# tweeq-Downloader_Basicv4.net
KiCad netlist of a schematic drawn in EAGLE
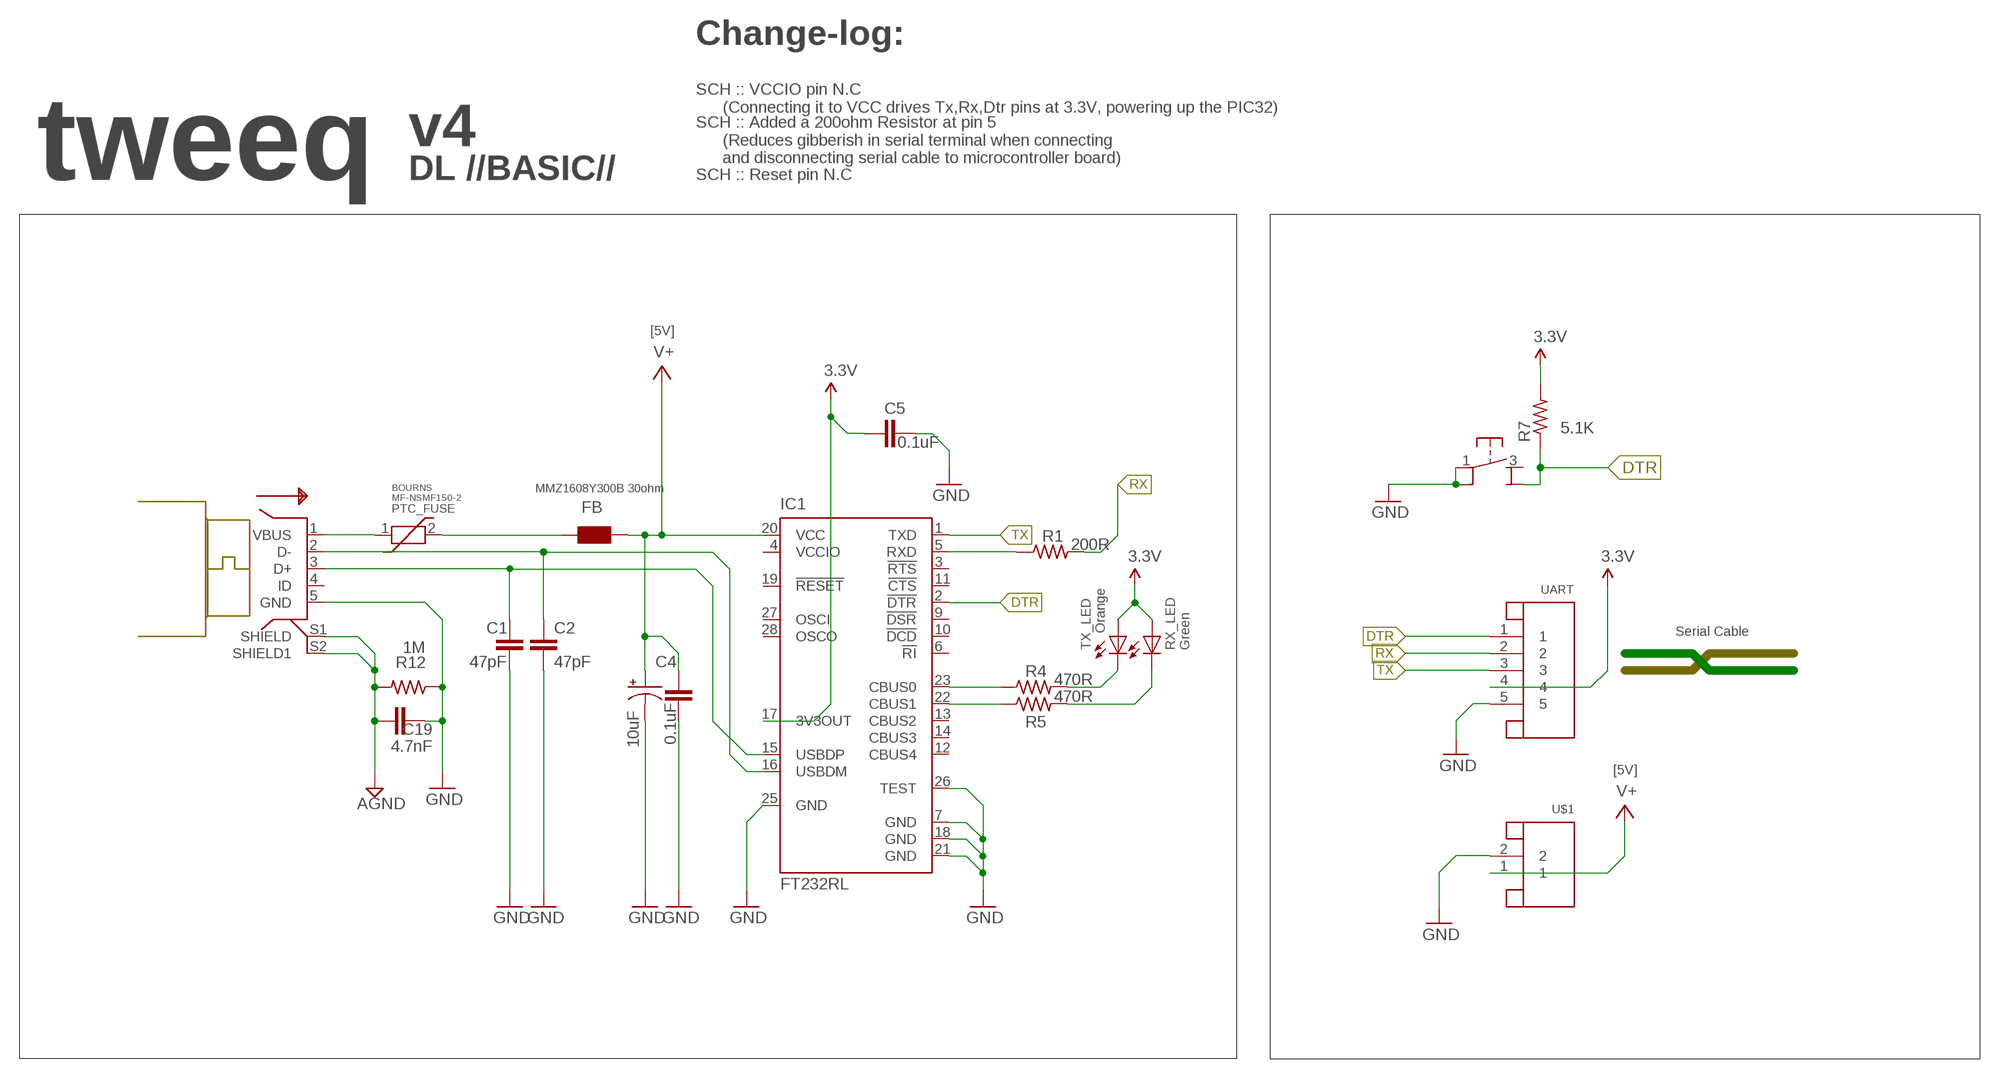
[diagram p0: schematic, sheet 1]

(export (version "E")
  (design (tool "Eeschema 10.0.6"))
  (components
    (comp (ref "C1")
      (value "47pF")
      (footprint "eagle-import:C0603K")
      (libsource (lib "eagle-import") (part "C-EUC0603K"))
    )
    (comp (ref "C2")
      (value "47pF")
      (footprint "eagle-import:C0603K")
      (libsource (lib "eagle-import") (part "C-EUC0603K"))
    )
    (comp (ref "C3")
      (value "10uF")
      (footprint "eagle-import:SMC_A")
      (libsource (lib "eagle-import") (part "CPOL-USSMCA"))
    )
    (comp (ref "C4")
      (value "0.1uF")
      (footprint "eagle-import:C0603K")
      (libsource (lib "eagle-import") (part "C-EUC0603K"))
    )
    (comp (ref "C5")
      (value "0.1uF")
      (footprint "eagle-import:C0603K")
      (libsource (lib "eagle-import") (part "C-EUC0603K"))
    )
    (comp (ref "C19")
      (value "4.7nF")
      (footprint "eagle-import:C0603K")
      (libsource (lib "eagle-import") (part "rcl_C-EUC0603K"))
    )
    (comp (ref "FB")
      (value "MMZ1608Y300B 30ohm")
      (footprint "eagle-import:0603")
      (libsource (lib "eagle-import") (part "WE-CBF_0603"))
    )
    (comp (ref "IC1")
      (value "FT232RL")
      (footprint "eagle-import:SSOP28")
      (libsource (lib "eagle-import") (part "FT232RL"))
    )
    (comp (ref "PTC_FUSE")
      (value "PTC_FUSE/MF-NSMF150-2")
      (footprint "eagle-import:1206F")
      (libsource (lib "eagle-import") (part "PTC_FUSE/MF-NSMF150-2"))
    )
    (comp (ref "R1")
      (value "200R")
      (footprint "eagle-import:R0603")
      (libsource (lib "eagle-import") (part "R-US_R0603"))
    )
    (comp (ref "R4")
      (value "470R")
      (footprint "eagle-import:R0603")
      (libsource (lib "eagle-import") (part "R-US_R0603"))
    )
    (comp (ref "R5")
      (value "470R")
      (footprint "eagle-import:R0603")
      (libsource (lib "eagle-import") (part "R-US_R0603"))
    )
    (comp (ref "R7")
      (value "5.1K")
      (footprint "eagle-import:R0603")
      (libsource (lib "eagle-import") (part "R-US_R0603"))
    )
    (comp (ref "R12")
      (value "1M")
      (footprint "eagle-import:R0603")
      (libsource (lib "eagle-import") (part "R-US_R0603"))
    )
    (comp (ref "RX_LED")
      (value "Green")
      (footprint "eagle-import:CHIP-LED0805")
      (libsource (lib "eagle-import") (part "LEDCHIP-LED0805"))
    )
    (comp (ref "TX_LED")
      (value "Orange")
      (footprint "eagle-import:CHIP-LED0805")
      (libsource (lib "eagle-import") (part "LEDCHIP-LED0805"))
    )
    (comp (ref "U$1")
      (value "JST-2PINSH")
      (footprint "eagle-import:SH1.0-2PIN")
      (libsource (lib "eagle-import") (part "JST-2PINSH"))
    )
    (comp (ref "U$2")
      (value "USB/MICRO-5PF-B")
      (footprint "eagle-import:MICRO_USB_5PF_B")
      (libsource (lib "eagle-import") (part "USB/MICRO-5PF-B"))
    )
    (comp (ref "U$4")
      (value "PB_MICRO_SMT")
      (footprint "eagle-import:PB_SMT_3.5X3X2")
      (libsource (lib "eagle-import") (part "PB_MICRO_SMT"))
    )
    (comp (ref "UART")
      (value "JST-5PINSH")
      (footprint "eagle-import:SH1.0-5PIN")
      (libsource (lib "eagle-import") (part "JST-5PINSH"))
    )
  )
  (nets
    (net (code "1") (name "/VCCIO") (class "Default")
      (node (ref "IC1") (pin "4") (pinfunction "VCCIO_4") (pintype "power_in"))
    )
    (net (code "2") (name "3.3V") (class "Default")
      (node (ref "C5") (pin "1") (pinfunction "1_1") (pintype "passive"))
      (node (ref "IC1") (pin "17") (pinfunction "3V3OUT_17") (pintype "output"))
      (node (ref "R7") (pin "2") (pinfunction "2_2") (pintype "passive"))
      (node (ref "RX_LED") (pin "A") (pinfunction "A_A") (pintype "passive"))
      (node (ref "TX_LED") (pin "A") (pinfunction "A_A") (pintype "passive"))
      (node (ref "UART") (pin "4") (pinfunction "4_4") (pintype "bidirectional"))
    )
    (net (code "3") (name "AGND") (class "Default")
      (node (ref "C19") (pin "2") (pinfunction "2_2") (pintype "passive"))
      (node (ref "R12") (pin "2") (pinfunction "2_2") (pintype "passive"))
      (node (ref "U$2") (pin "S1") (pinfunction "SHIELD_S1") (pintype "bidirectional"))
      (node (ref "U$2") (pin "S2") (pinfunction "SHIELD1_S2") (pintype "bidirectional"))
    )
    (net (code "4") (name "DTR") (class "Default")
      (node (ref "IC1") (pin "2") (pinfunction "~{DTR}_2") (pintype "output"))
      (node (ref "R7") (pin "1") (pinfunction "1_1") (pintype "passive"))
      (node (ref "U$4") (pin "4") (pinfunction "2A_4") (pintype "passive"))
      (node (ref "UART") (pin "1") (pinfunction "1_1") (pintype "bidirectional"))
    )
    (net (code "5") (name "GND") (class "Default")
      (node (ref "C1") (pin "2") (pinfunction "2_2") (pintype "passive"))
      (node (ref "C19") (pin "1") (pinfunction "1_1") (pintype "passive"))
      (node (ref "C2") (pin "2") (pinfunction "2_2") (pintype "passive"))
      (node (ref "C3") (pin "-") (pinfunction "-_-") (pintype "passive"))
      (node (ref "C4") (pin "2") (pinfunction "2_2") (pintype "passive"))
      (node (ref "C5") (pin "2") (pinfunction "2_2") (pintype "passive"))
      (node (ref "IC1") (pin "18") (pinfunction "GND_18") (pintype "power_in"))
      (node (ref "IC1") (pin "21") (pinfunction "GND_21") (pintype "power_in"))
      (node (ref "IC1") (pin "25") (pinfunction "GND_25") (pintype "power_in"))
      (node (ref "IC1") (pin "26") (pinfunction "TEST_26") (pintype "input"))
      (node (ref "IC1") (pin "7") (pinfunction "GND_7") (pintype "power_in"))
      (node (ref "R12") (pin "1") (pinfunction "1_1") (pintype "passive"))
      (node (ref "U$1") (pin "2") (pinfunction "2_2") (pintype "bidirectional"))
      (node (ref "U$2") (pin "5") (pinfunction "GND_5") (pintype "bidirectional"))
      (node (ref "U$4") (pin "1") (pinfunction "1_1") (pintype "passive"))
      (node (ref "U$4") (pin "2") (pinfunction "1A_2") (pintype "passive"))
      (node (ref "UART") (pin "5") (pinfunction "5_5") (pintype "bidirectional"))
    )
    (net (code "6") (name "Net-(FB-Pad2)") (class "Default")
      (node (ref "FB") (pin "2") (pinfunction "2_2") (pintype "passive"))
      (node (ref "PTC_FUSE") (pin "2") (pinfunction "2_2") (pintype "bidirectional"))
    )
    (net (code "7") (name "Net-(IC1-CBUS0)") (class "Default")
      (node (ref "IC1") (pin "23") (pinfunction "CBUS0_23") (pintype "bidirectional"))
      (node (ref "R4") (pin "1") (pinfunction "1_1") (pintype "passive"))
    )
    (net (code "8") (name "Net-(IC1-CBUS1)") (class "Default")
      (node (ref "IC1") (pin "22") (pinfunction "CBUS1_22") (pintype "bidirectional"))
      (node (ref "R5") (pin "1") (pinfunction "1_1") (pintype "passive"))
    )
    (net (code "9") (name "Net-(IC1-RXD)") (class "Default")
      (node (ref "IC1") (pin "5") (pinfunction "RXD_5") (pintype "input"))
      (node (ref "R1") (pin "1") (pinfunction "1_1") (pintype "passive"))
    )
    (net (code "10") (name "Net-(IC1-USBDM)") (class "Default")
      (node (ref "C2") (pin "1") (pinfunction "1_1") (pintype "passive"))
      (node (ref "IC1") (pin "16") (pinfunction "USBDM_16") (pintype "bidirectional"))
      (node (ref "U$2") (pin "2") (pinfunction "D-_2") (pintype "bidirectional"))
    )
    (net (code "11") (name "Net-(IC1-USBDP)") (class "Default")
      (node (ref "C1") (pin "1") (pinfunction "1_1") (pintype "passive"))
      (node (ref "IC1") (pin "15") (pinfunction "USBDP_15") (pintype "bidirectional"))
      (node (ref "U$2") (pin "3") (pinfunction "D+_3") (pintype "bidirectional"))
    )
    (net (code "12") (name "Net-(R4-Pad2)") (class "Default")
      (node (ref "R4") (pin "2") (pinfunction "2_2") (pintype "passive"))
      (node (ref "TX_LED") (pin "C") (pinfunction "C_C") (pintype "passive"))
    )
    (net (code "13") (name "Net-(R5-Pad2)") (class "Default")
      (node (ref "R5") (pin "2") (pinfunction "2_2") (pintype "passive"))
      (node (ref "RX_LED") (pin "C") (pinfunction "C_C") (pintype "passive"))
    )
    (net (code "14") (name "Net-(U$2-VBUS)") (class "Default")
      (node (ref "PTC_FUSE") (pin "1") (pinfunction "1_1") (pintype "bidirectional"))
      (node (ref "U$2") (pin "1") (pinfunction "VBUS_1") (pintype "bidirectional"))
    )
    (net (code "15") (name "RX") (class "Default")
      (node (ref "R1") (pin "2") (pinfunction "2_2") (pintype "passive"))
      (node (ref "UART") (pin "2") (pinfunction "2_2") (pintype "bidirectional"))
    )
    (net (code "16") (name "TX") (class "Default")
      (node (ref "IC1") (pin "1") (pinfunction "TXD_1") (pintype "output"))
      (node (ref "UART") (pin "3") (pinfunction "3_3") (pintype "bidirectional"))
    )
    (net (code "17") (name "V+") (class "Default")
      (node (ref "C3") (pin "+") (pinfunction "+_+") (pintype "passive"))
      (node (ref "C4") (pin "1") (pinfunction "1_1") (pintype "passive"))
      (node (ref "FB") (pin "1") (pinfunction "1_1") (pintype "passive"))
      (node (ref "IC1") (pin "20") (pinfunction "VCC_20") (pintype "power_in"))
      (node (ref "U$1") (pin "1") (pinfunction "1_1") (pintype "bidirectional"))
    )
    (net (code "18") (name "unconnected-(IC1-CBUS2-Pad13)") (class "Default")
      (node (ref "IC1") (pin "13") (pinfunction "CBUS2_13") (pintype "bidirectional"))
    )
    (net (code "19") (name "unconnected-(IC1-CBUS3-Pad14)") (class "Default")
      (node (ref "IC1") (pin "14") (pinfunction "CBUS3_14") (pintype "bidirectional"))
    )
    (net (code "20") (name "unconnected-(IC1-CBUS4-Pad12)") (class "Default")
      (node (ref "IC1") (pin "12") (pinfunction "CBUS4_12") (pintype "bidirectional"))
    )
    (net (code "21") (name "unconnected-(IC1-OSCI-Pad27)") (class "Default")
      (node (ref "IC1") (pin "27") (pinfunction "OSCI_27") (pintype "input"))
    )
    (net (code "22") (name "unconnected-(IC1-OSCO-Pad28)") (class "Default")
      (node (ref "IC1") (pin "28") (pinfunction "OSCO_28") (pintype "output"))
    )
    (net (code "23") (name "unconnected-(IC1-~{CTS}-Pad11)") (class "Default")
      (node (ref "IC1") (pin "11") (pinfunction "~{CTS}_11") (pintype "input"))
    )
    (net (code "24") (name "unconnected-(IC1-~{DCD}-Pad10)") (class "Default")
      (node (ref "IC1") (pin "10") (pinfunction "~{DCD}_10") (pintype "input"))
    )
    (net (code "25") (name "unconnected-(IC1-~{DSR}-Pad9)") (class "Default")
      (node (ref "IC1") (pin "9") (pinfunction "~{DSR}_9") (pintype "input"))
    )
    (net (code "26") (name "unconnected-(IC1-~{RESET}-Pad19)") (class "Default")
      (node (ref "IC1") (pin "19") (pinfunction "~{RESET}_19") (pintype "input"))
    )
    (net (code "27") (name "unconnected-(IC1-~{RI}-Pad6)") (class "Default")
      (node (ref "IC1") (pin "6") (pinfunction "~{RI}_6") (pintype "input"))
    )
    (net (code "28") (name "unconnected-(IC1-~{RTS}-Pad3)") (class "Default")
      (node (ref "IC1") (pin "3") (pinfunction "~{RTS}_3") (pintype "output"))
    )
    (net (code "29") (name "unconnected-(U$2-ID-Pad4)") (class "Default")
      (node (ref "U$2") (pin "4") (pinfunction "ID_4") (pintype "bidirectional"))
    )
    (net (code "30") (name "unconnected-(U$4-2-Pad3)") (class "Default")
      (node (ref "U$4") (pin "3") (pinfunction "2_3") (pintype "passive"))
    )
  )
)
